# charger.net
KiCad netlist of a schematic drawn in Altium Designer
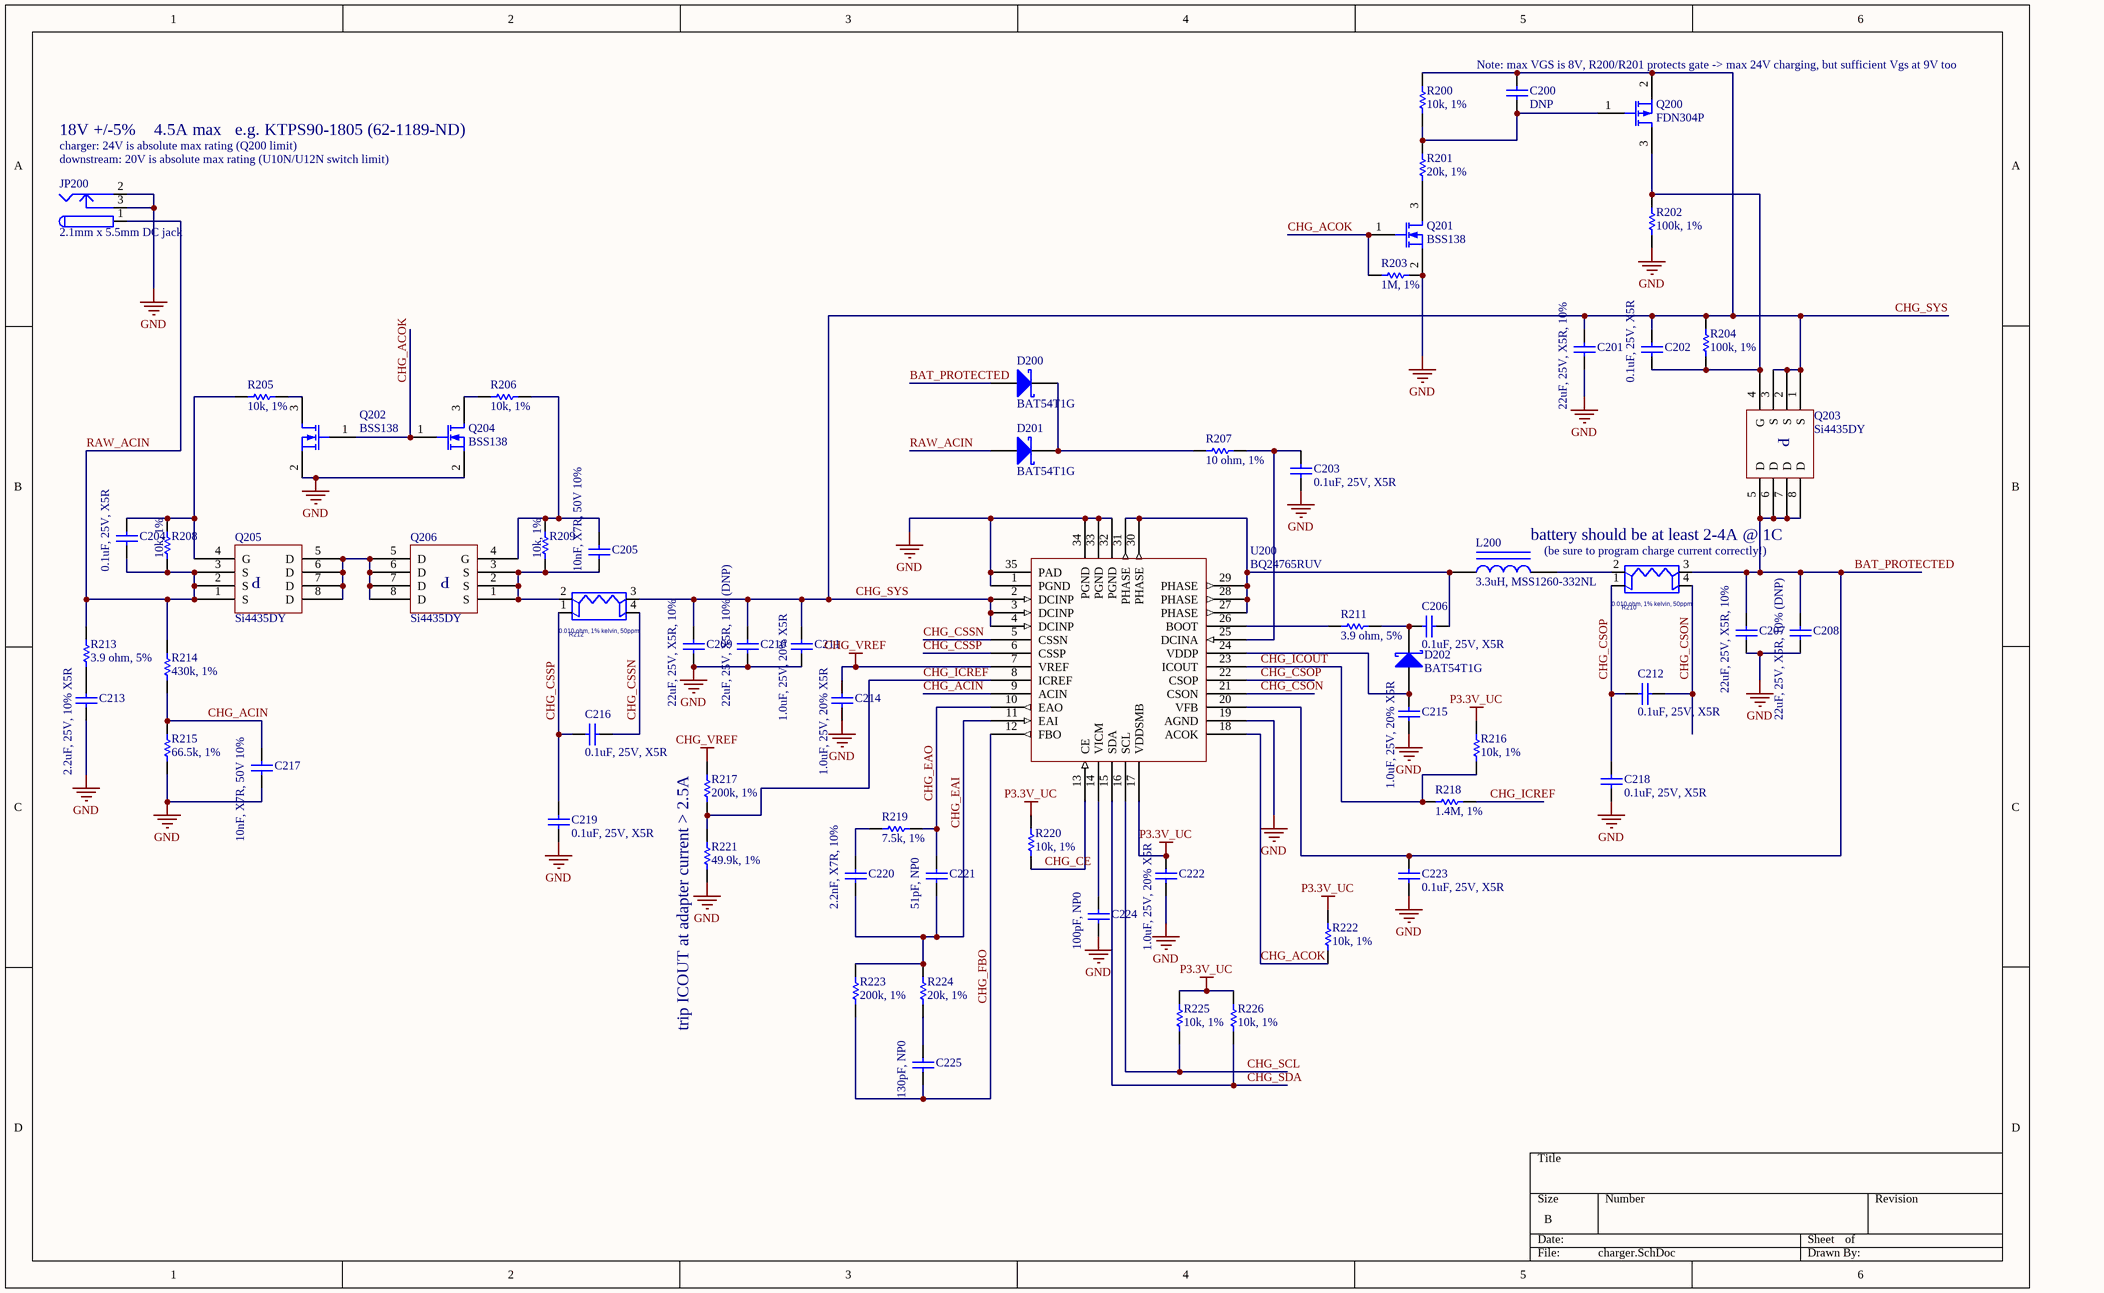
[diagram p0: charger.SchDoc]

(export (version "E")
  (design (tool "Eeschema 10.0.6"))
  (components
    (comp (ref "C200")
      (value "DNP")
      (footprint "CAPC1005N")
      (description "Capacitor (Semiconductor SIM Model)")
      (fields (field (name "PUBLISHER") "Altium Limited"))
      (libsource (lib "Miscellaneous Devices") (part "Cap Semi"))
    )
    (comp (ref "C201")
      (value "22uF, 25V, X5R, 10%")
      (footprint "CAPC3225N")
      (description "Capacitor (Semiconductor SIM Model)")
      (fields (field (name "PUBLISHER") "Altium Limited"))
      (libsource (lib "Miscellaneous Devices") (part "Cap Semi"))
    )
    (comp (ref "C202")
      (value "0.1uF, 25V, X5R")
      (footprint "CAPC1005N")
      (description "Capacitor (Semiconductor SIM Model)")
      (fields (field (name "PUBLISHER") "Altium Limited"))
      (libsource (lib "Miscellaneous Devices") (part "Cap Semi"))
    )
    (comp (ref "C203")
      (value "0.1uF, 25V, X5R")
      (footprint "CAPC1005N")
      (description "Capacitor (Semiconductor SIM Model)")
      (fields (field (name "PUBLISHER") "Altium Limited"))
      (libsource (lib "Miscellaneous Devices") (part "Cap Semi"))
    )
    (comp (ref "C204")
      (value "0.1uF, 25V, X5R")
      (footprint "CAPC1005N")
      (description "Capacitor (Semiconductor SIM Model)")
      (fields (field (name "PUBLISHER") "Altium Limited"))
      (libsource (lib "Miscellaneous Devices") (part "Cap Semi"))
    )
    (comp (ref "C205")
      (value "10nF, X7R, 50V 10%")
      (footprint "CAPC1005N")
      (description "Capacitor (Semiconductor SIM Model)")
      (fields (field (name "PUBLISHER") "Altium Limited"))
      (libsource (lib "Miscellaneous Devices") (part "Cap Semi"))
    )
    (comp (ref "C206")
      (value "0.1uF, 25V, X5R")
      (footprint "CAPC1005N")
      (description "Capacitor (Semiconductor SIM Model)")
      (fields (field (name "PUBLISHER") "Altium Limited"))
      (libsource (lib "Miscellaneous Devices") (part "Cap Semi"))
    )
    (comp (ref "C207")
      (value "22uF, 25V, X5R, 10%")
      (footprint "CAPC3225N")
      (description "Capacitor (Semiconductor SIM Model)")
      (fields (field (name "PUBLISHER") "Altium Limited"))
      (libsource (lib "Miscellaneous Devices") (part "Cap Semi"))
    )
    (comp (ref "C208")
      (value "22uF, 25V, X5R, 10% (DNP)")
      (footprint "CAPC3225N")
      (description "Capacitor (Semiconductor SIM Model)")
      (fields (field (name "PUBLISHER") "Altium Limited"))
      (libsource (lib "Miscellaneous Devices") (part "Cap Semi"))
    )
    (comp (ref "C209")
      (value "22uF, 25V, X5R, 10%")
      (footprint "CAPC3225N")
      (description "Capacitor (Semiconductor SIM Model)")
      (fields (field (name "PUBLISHER") "Altium Limited"))
      (libsource (lib "Miscellaneous Devices") (part "Cap Semi"))
    )
    (comp (ref "C210")
      (value "22uF, 25V, X5R, 10% (DNP)")
      (footprint "CAPC3225N")
      (description "Capacitor (Semiconductor SIM Model)")
      (fields (field (name "PUBLISHER") "Altium Limited"))
      (libsource (lib "Miscellaneous Devices") (part "Cap Semi"))
    )
    (comp (ref "C211")
      (value "1.0uF, 25V, 20% X5R")
      (footprint "CAPC1608N")
      (description "Capacitor (Semiconductor SIM Model)")
      (fields (field (name "PUBLISHER") "Altium Limited"))
      (libsource (lib "Miscellaneous Devices") (part "Cap Semi"))
    )
    (comp (ref "C212")
      (value "0.1uF, 25V, X5R")
      (footprint "CAPC1005N")
      (description "Capacitor (Semiconductor SIM Model)")
      (fields (field (name "PUBLISHER") "Altium Limited"))
      (libsource (lib "Miscellaneous Devices") (part "Cap Semi"))
    )
    (comp (ref "C213")
      (value "2.2uF, 25V, 10% X5R")
      (footprint "CAPC1608N")
      (description "Capacitor (Semiconductor SIM Model)")
      (fields (field (name "PUBLISHER") "Altium Limited"))
      (libsource (lib "Miscellaneous Devices") (part "Cap Semi"))
    )
    (comp (ref "C214")
      (value "1.0uF, 25V, 20% X5R")
      (footprint "CAPC1608N")
      (description "Capacitor (Semiconductor SIM Model)")
      (fields (field (name "PUBLISHER") "Altium Limited"))
      (libsource (lib "Miscellaneous Devices") (part "Cap Semi"))
    )
    (comp (ref "C215")
      (value "1.0uF, 25V, 20% X5R")
      (footprint "CAPC1608N")
      (description "Capacitor (Semiconductor SIM Model)")
      (fields (field (name "PUBLISHER") "Altium Limited"))
      (libsource (lib "Miscellaneous Devices") (part "Cap Semi"))
    )
    (comp (ref "C216")
      (value "0.1uF, 25V, X5R")
      (footprint "CAPC1005N")
      (description "Capacitor (Semiconductor SIM Model)")
      (fields (field (name "PUBLISHER") "Altium Limited"))
      (libsource (lib "Miscellaneous Devices") (part "Cap Semi"))
    )
    (comp (ref "C217")
      (value "10nF, X7R, 50V 10%")
      (footprint "CAPC1005N")
      (description "Capacitor (Semiconductor SIM Model)")
      (fields (field (name "PUBLISHER") "Altium Limited"))
      (libsource (lib "Miscellaneous Devices") (part "Cap Semi"))
    )
    (comp (ref "C218")
      (value "0.1uF, 25V, X5R")
      (footprint "CAPC1005N")
      (description "Capacitor (Semiconductor SIM Model)")
      (fields (field (name "PUBLISHER") "Altium Limited"))
      (libsource (lib "Miscellaneous Devices") (part "Cap Semi"))
    )
    (comp (ref "C219")
      (value "0.1uF, 25V, X5R")
      (footprint "CAPC1005N")
      (description "Capacitor (Semiconductor SIM Model)")
      (fields (field (name "PUBLISHER") "Altium Limited"))
      (libsource (lib "Miscellaneous Devices") (part "Cap Semi"))
    )
    (comp (ref "C220")
      (value "2.2nF, X7R, 10%")
      (footprint "CAPC1005N")
      (description "Capacitor (Semiconductor SIM Model)")
      (fields (field (name "PUBLISHER") "Altium Limited"))
      (libsource (lib "Miscellaneous Devices") (part "Cap Semi"))
    )
    (comp (ref "C221")
      (value "51pF, NP0")
      (footprint "CAPC1005N")
      (description "Capacitor (Semiconductor SIM Model)")
      (fields (field (name "PUBLISHER") "Altium Limited"))
      (libsource (lib "Miscellaneous Devices") (part "Cap Semi"))
    )
    (comp (ref "C222")
      (value "1.0uF, 25V, 20% X5R")
      (footprint "CAPC1608N")
      (description "Capacitor (Semiconductor SIM Model)")
      (fields (field (name "PUBLISHER") "Altium Limited"))
      (libsource (lib "Miscellaneous Devices") (part "Cap Semi"))
    )
    (comp (ref "C223")
      (value "0.1uF, 25V, X5R")
      (footprint "CAPC1005N")
      (description "Capacitor (Semiconductor SIM Model)")
      (fields (field (name "PUBLISHER") "Altium Limited"))
      (libsource (lib "Miscellaneous Devices") (part "Cap Semi"))
    )
    (comp (ref "C224")
      (value "100pF, NP0")
      (footprint "CAPC1005N")
      (description "Capacitor (Semiconductor SIM Model)")
      (fields (field (name "PUBLISHER") "Altium Limited"))
      (libsource (lib "Miscellaneous Devices") (part "Cap Semi"))
    )
    (comp (ref "C225")
      (value "130pF, NP0")
      (footprint "CAPC1005N")
      (description "Capacitor (Semiconductor SIM Model)")
      (fields (field (name "PUBLISHER") "Altium Limited"))
      (libsource (lib "Miscellaneous Devices") (part "Cap Semi"))
    )
    (comp (ref "D200")
      (value "BAT54T1G")
      (footprint "SOD123")
      (description "Schottky Diode")
      (fields (field (name "PUBLISHER") "Altium Limited"))
      (libsource (lib "Miscellaneous Devices") (part "D Schottky"))
    )
    (comp (ref "D201")
      (value "BAT54T1G")
      (footprint "SOD123")
      (description "Schottky Diode")
      (fields (field (name "PUBLISHER") "Altium Limited"))
      (libsource (lib "Miscellaneous Devices") (part "D Schottky"))
    )
    (comp (ref "D202")
      (value "BAT54T1G")
      (footprint "SOD123")
      (description "Schottky Diode")
      (fields (field (name "PUBLISHER") "Altium Limited"))
      (libsource (lib "Miscellaneous Devices") (part "D Schottky"))
    )
    (comp (ref "JP200")
      (value "2.1mm x 5.5mm DC jack")
      (footprint "CUI_PJ_002AH_SMT")
      (description "Low Voltage Power Supply Connector")
      (fields (field (name "PUBLISHER") "Altium Limited"))
      (libsource (lib "Miscellaneous Connectors") (part "PWR2.5"))
    )
    (comp (ref "L200")
      (value "3.3uH, MSS1260-332NL")
      (footprint "COILCRAFT_MSS1048")
      (description "Magnetic-Core Inductor")
      (fields (field (name "PUBLISHER") "Altium Limited"))
      (libsource (lib "Miscellaneous Devices") (part "Inductor Iron"))
    )
    (comp (ref "Q200")
      (value "FDN304P")
      (footprint "SOT23-3N")
      (description "P-Channel MOSFET")
      (fields (field (name "PUBLISHER") "Altium Limited"))
      (libsource (lib "Miscellaneous Devices") (part "MOSFET-P"))
    )
    (comp (ref "Q201")
      (value "BSS138")
      (footprint "SOT23-3N")
      (description "N-Channel MOSFET")
      (fields (field (name "PUBLISHER") "Altium Limited"))
      (libsource (lib "Miscellaneous Devices") (part "MOSFET-N"))
    )
    (comp (ref "Q202")
      (value "BSS138")
      (footprint "SOT23-3N")
      (description "N-Channel MOSFET")
      (fields (field (name "PUBLISHER") "Altium Limited"))
      (libsource (lib "Miscellaneous Devices") (part "MOSFET-N"))
    )
    (comp (ref "Q203")
      (value "Si4435DY")
      (footprint "SOIC127P600-8AN")
      (description "Singre P-channel FET, 8A, 30V")
      (libsource (lib "") (part "Si4435DY_2"))
    )
    (comp (ref "Q204")
      (value "BSS138")
      (footprint "SOT23-3N")
      (description "N-Channel MOSFET")
      (fields (field (name "PUBLISHER") "Altium Limited"))
      (libsource (lib "Miscellaneous Devices") (part "MOSFET-N"))
    )
    (comp (ref "Q205")
      (value "Si4435DY")
      (footprint "SOIC127P600-8AN")
      (description "Singre P-channel FET, 8A, 30V")
      (libsource (lib "") (part "Si4435DY_1"))
    )
    (comp (ref "Q206")
      (value "Si4435DY")
      (footprint "SOIC127P600-8AN")
      (description "Singre P-channel FET, 8A, 30V")
      (libsource (lib "commonsch") (part "Si4435DY"))
    )
    (comp (ref "R200")
      (value "10k, 1%")
      (footprint "RESC1005N")
      (description "Resistor")
      (fields (field (name "PUBLISHER") "Altium Limited"))
      (libsource (lib "Miscellaneous Devices") (part "Res1"))
    )
    (comp (ref "R201")
      (value "20k, 1%")
      (footprint "RESC1005N")
      (description "Resistor")
      (fields (field (name "PUBLISHER") "Altium Limited"))
      (libsource (lib "Miscellaneous Devices") (part "Res1"))
    )
    (comp (ref "R202")
      (value "100k, 1%")
      (footprint "RESC1005N")
      (description "Resistor")
      (fields (field (name "PUBLISHER") "Altium Limited"))
      (libsource (lib "Miscellaneous Devices") (part "Res1"))
    )
    (comp (ref "R203")
      (value "1M, 1%")
      (footprint "RESC1005N")
      (description "Resistor")
      (fields (field (name "PUBLISHER") "Altium Limited"))
      (libsource (lib "Miscellaneous Devices") (part "Res1"))
    )
    (comp (ref "R204")
      (value "100k, 1%")
      (footprint "RESC1005N")
      (description "Resistor")
      (fields (field (name "PUBLISHER") "Altium Limited"))
      (libsource (lib "Miscellaneous Devices") (part "Res1"))
    )
    (comp (ref "R205")
      (value "10k, 1%")
      (footprint "RESC1005N")
      (description "Resistor")
      (fields (field (name "PUBLISHER") "Altium Limited"))
      (libsource (lib "Miscellaneous Devices") (part "Res1"))
    )
    (comp (ref "R206")
      (value "10k, 1%")
      (footprint "RESC1005N")
      (description "Resistor")
      (fields (field (name "PUBLISHER") "Altium Limited"))
      (libsource (lib "Miscellaneous Devices") (part "Res1"))
    )
    (comp (ref "R207")
      (value "10 ohm, 1%")
      (footprint "RESC1005N")
      (description "Resistor")
      (fields (field (name "PUBLISHER") "Altium Limited"))
      (libsource (lib "Miscellaneous Devices") (part "Res1"))
    )
    (comp (ref "R208")
      (value "10k, 1%")
      (footprint "RESC1005N")
      (description "Resistor")
      (fields (field (name "PUBLISHER") "Altium Limited"))
      (libsource (lib "Miscellaneous Devices") (part "Res1"))
    )
    (comp (ref "R209")
      (value "10k, 1%")
      (footprint "RESC1005N")
      (description "Resistor")
      (fields (field (name "PUBLISHER") "Altium Limited"))
      (libsource (lib "Miscellaneous Devices") (part "Res1"))
    )
    (comp (ref "R210")
      (value "0.010 ohm, 1% kelvin, 50ppm")
      (fields
        (field (name "PART_NUMBER") "R00034-001")
        (field (name "TOLERANCE") "?")
        (field (name "MFG") "OHMITE")
      )
      (libsource (lib "*") (part "RES_4TERM"))
    )
    (comp (ref "R211")
      (value "3.9 ohm, 5%")
      (footprint "RESC1005N")
      (description "Resistor")
      (fields (field (name "PUBLISHER") "Altium Limited"))
      (libsource (lib "Miscellaneous Devices") (part "Res1"))
    )
    (comp (ref "R212")
      (value "0.010 ohm, 1% kelvin, 50ppm")
      (fields
        (field (name "PART_NUMBER") "R00034-001")
        (field (name "TOLERANCE") "?")
        (field (name "MFG") "OHMITE")
      )
      (libsource (lib "*") (part "RES_4TERM"))
    )
    (comp (ref "R213")
      (value "3.9 ohm, 5%")
      (footprint "RESC1005N")
      (description "Resistor")
      (fields (field (name "PUBLISHER") "Altium Limited"))
      (libsource (lib "Miscellaneous Devices") (part "Res1"))
    )
    (comp (ref "R214")
      (value "430k, 1%")
      (footprint "RESC1005N")
      (description "Resistor")
      (fields (field (name "PUBLISHER") "Altium Limited"))
      (libsource (lib "Miscellaneous Devices") (part "Res1"))
    )
    (comp (ref "R215")
      (value "66.5k, 1%")
      (footprint "RESC1005N")
      (description "Resistor")
      (fields (field (name "PUBLISHER") "Altium Limited"))
      (libsource (lib "Miscellaneous Devices") (part "Res1"))
    )
    (comp (ref "R216")
      (value "10k, 1%")
      (footprint "RESC1005N")
      (description "Resistor")
      (fields (field (name "PUBLISHER") "Altium Limited"))
      (libsource (lib "Miscellaneous Devices") (part "Res1"))
    )
    (comp (ref "R217")
      (value "200k, 1%")
      (footprint "RESC1005N")
      (description "Resistor")
      (fields (field (name "PUBLISHER") "Altium Limited"))
      (libsource (lib "Miscellaneous Devices") (part "Res1"))
    )
    (comp (ref "R218")
      (value "1.4M, 1%")
      (footprint "RESC1005N")
      (description "Resistor")
      (fields (field (name "PUBLISHER") "Altium Limited"))
      (libsource (lib "Miscellaneous Devices") (part "Res1"))
    )
    (comp (ref "R219")
      (value "7.5k, 1%")
      (footprint "RESC1005N")
      (description "Resistor")
      (fields (field (name "PUBLISHER") "Altium Limited"))
      (libsource (lib "Miscellaneous Devices") (part "Res1"))
    )
    (comp (ref "R220")
      (value "10k, 1%")
      (footprint "RESC1005N")
      (description "Resistor")
      (fields (field (name "PUBLISHER") "Altium Limited"))
      (libsource (lib "Miscellaneous Devices") (part "Res1"))
    )
    (comp (ref "R221")
      (value "49.9k, 1%")
      (footprint "RESC1005N")
      (description "Resistor")
      (fields (field (name "PUBLISHER") "Altium Limited"))
      (libsource (lib "Miscellaneous Devices") (part "Res1"))
    )
    (comp (ref "R222")
      (value "10k, 1%")
      (footprint "RESC1005N")
      (description "Resistor")
      (fields (field (name "PUBLISHER") "Altium Limited"))
      (libsource (lib "Miscellaneous Devices") (part "Res1"))
    )
    (comp (ref "R223")
      (value "200k, 1%")
      (footprint "RESC1005N")
      (description "Resistor")
      (fields (field (name "PUBLISHER") "Altium Limited"))
      (libsource (lib "Miscellaneous Devices") (part "Res1"))
    )
    (comp (ref "R224")
      (value "20k, 1%")
      (footprint "RESC1005N")
      (description "Resistor")
      (fields (field (name "PUBLISHER") "Altium Limited"))
      (libsource (lib "Miscellaneous Devices") (part "Res1"))
    )
    (comp (ref "R225")
      (value "10k, 1%")
      (footprint "RESC1005N")
      (description "Resistor")
      (fields (field (name "PUBLISHER") "Altium Limited"))
      (libsource (lib "Miscellaneous Devices") (part "Res1"))
    )
    (comp (ref "R226")
      (value "10k, 1%")
      (footprint "RESC1005N")
      (description "Resistor")
      (fields (field (name "PUBLISHER") "Altium Limited"))
      (libsource (lib "Miscellaneous Devices") (part "Res1"))
    )
    (comp (ref "U200")
      (value "BQ24765RUV")
      (footprint "TI_R-PVQFN-N34")
      (description "SMBus-controlled battery charger with integrated FETs")
      (libsource (lib "commonsch") (part "BQ24765RUV"))
    )
  )
  (nets
    (net (code "1") (name "/BAT_PROTECTED") (class "Default")
      (node (ref "C207") (pin "1") (pinfunction "1_1") (pintype "passive"))
      (node (ref "C208") (pin "1") (pinfunction "1_1") (pintype "passive"))
      (node (ref "C223") (pin "2") (pinfunction "2_2") (pintype "passive"))
      (node (ref "D200") (pin "1") (pinfunction "A_1") (pintype "passive"))
      (node (ref "Q203") (pin "5") (pinfunction "D_5") (pintype "passive"))
      (node (ref "Q203") (pin "6") (pinfunction "D_6") (pintype "passive"))
      (node (ref "Q203") (pin "7") (pinfunction "D_7") (pintype "passive"))
      (node (ref "Q203") (pin "8") (pinfunction "D_8") (pintype "passive"))
      (node (ref "R210") (pin "3") (pinfunction "3_3") (pintype "bidirectional"))
      (node (ref "U200") (pin "20") (pinfunction "VFB_20") (pintype "passive"))
    )
    (net (code "2") (name "/CHG_ACIN") (class "Default")
      (node (ref "C217") (pin "1") (pinfunction "1_1") (pintype "passive"))
      (node (ref "R214") (pin "2") (pinfunction "2_2") (pintype "passive"))
      (node (ref "R215") (pin "1") (pinfunction "1_1") (pintype "passive"))
      (node (ref "U200") (pin "9") (pinfunction "ACIN_9") (pintype "passive"))
    )
    (net (code "3") (name "/CHG_ACOK") (class "Default")
      (node (ref "Q201") (pin "1") (pinfunction "G_1") (pintype "passive"))
      (node (ref "Q202") (pin "1") (pinfunction "G_1") (pintype "passive"))
      (node (ref "Q204") (pin "1") (pinfunction "G_1") (pintype "passive"))
      (node (ref "R203") (pin "2") (pinfunction "2_2") (pintype "passive"))
      (node (ref "R222") (pin "2") (pinfunction "2_2") (pintype "passive"))
      (node (ref "U200") (pin "18") (pinfunction "ACOK_18") (pintype "open_collector"))
    )
    (net (code "4") (name "/CHG_CE") (class "Default")
      (node (ref "R220") (pin "2") (pinfunction "2_2") (pintype "passive"))
      (node (ref "U200") (pin "13") (pinfunction "CE_13") (pintype "input"))
    )
    (net (code "5") (name "/CHG_CSON") (class "Default")
      (node (ref "C212") (pin "1") (pinfunction "1_1") (pintype "passive"))
      (node (ref "R210") (pin "4") (pinfunction "4_4") (pintype "bidirectional"))
      (node (ref "U200") (pin "21") (pinfunction "CSON_21") (pintype "passive"))
    )
    (net (code "6") (name "/CHG_CSOP") (class "Default")
      (node (ref "C212") (pin "2") (pinfunction "2_2") (pintype "passive"))
      (node (ref "C218") (pin "2") (pinfunction "2_2") (pintype "passive"))
      (node (ref "R210") (pin "1") (pinfunction "1_1") (pintype "bidirectional"))
      (node (ref "U200") (pin "22") (pinfunction "CSOP_22") (pintype "passive"))
    )
    (net (code "7") (name "/CHG_CSSN") (class "Default")
      (node (ref "C216") (pin "2") (pinfunction "2_2") (pintype "passive"))
      (node (ref "R212") (pin "4") (pinfunction "4_4") (pintype "bidirectional"))
      (node (ref "U200") (pin "5") (pinfunction "CSSN_5") (pintype "passive"))
    )
    (net (code "8") (name "/CHG_CSSP") (class "Default")
      (node (ref "C216") (pin "1") (pinfunction "1_1") (pintype "passive"))
      (node (ref "C219") (pin "1") (pinfunction "1_1") (pintype "passive"))
      (node (ref "R212") (pin "1") (pinfunction "1_1") (pintype "bidirectional"))
      (node (ref "U200") (pin "6") (pinfunction "CSSP_6") (pintype "passive"))
    )
    (net (code "9") (name "/CHG_EAI") (class "Default")
      (node (ref "C220") (pin "2") (pinfunction "2_2") (pintype "passive"))
      (node (ref "C221") (pin "2") (pinfunction "2_2") (pintype "passive"))
      (node (ref "R223") (pin "1") (pinfunction "1_1") (pintype "passive"))
      (node (ref "R224") (pin "1") (pinfunction "1_1") (pintype "passive"))
      (node (ref "U200") (pin "11") (pinfunction "EAI_11") (pintype "input"))
    )
    (net (code "10") (name "/CHG_EAO") (class "Default")
      (node (ref "C221") (pin "1") (pinfunction "1_1") (pintype "passive"))
      (node (ref "R219") (pin "2") (pinfunction "2_2") (pintype "passive"))
      (node (ref "U200") (pin "10") (pinfunction "EAO_10") (pintype "output"))
    )
    (net (code "11") (name "/CHG_FBO") (class "Default")
      (node (ref "C225") (pin "2") (pinfunction "2_2") (pintype "passive"))
      (node (ref "R223") (pin "2") (pinfunction "2_2") (pintype "passive"))
      (node (ref "U200") (pin "12") (pinfunction "FBO_12") (pintype "output"))
    )
    (net (code "12") (name "/CHG_ICOUT") (class "Default")
      (node (ref "R216") (pin "2") (pinfunction "2_2") (pintype "passive"))
      (node (ref "R218") (pin "2") (pinfunction "2_2") (pintype "passive"))
      (node (ref "U200") (pin "23") (pinfunction "ICOUT_23") (pintype "open_collector"))
    )
    (net (code "13") (name "/CHG_ICREF") (class "Default")
      (node (ref "R217") (pin "2") (pinfunction "2_2") (pintype "passive"))
      (node (ref "R218") (pin "1") (pinfunction "1_1") (pintype "passive"))
      (node (ref "R221") (pin "1") (pinfunction "1_1") (pintype "passive"))
      (node (ref "U200") (pin "8") (pinfunction "ICREF_8") (pintype "passive"))
    )
    (net (code "14") (name "/CHG_SCL") (class "Default")
      (node (ref "R225") (pin "2") (pinfunction "2_2") (pintype "passive"))
      (node (ref "U200") (pin "16") (pinfunction "SCL_16") (pintype "open_emitter"))
    )
    (net (code "15") (name "/CHG_SDA") (class "Default")
      (node (ref "R226") (pin "2") (pinfunction "2_2") (pintype "passive"))
      (node (ref "U200") (pin "15") (pinfunction "SDA_15") (pintype "open_emitter"))
    )
    (net (code "16") (name "/CHG_SYS") (class "Default")
      (node (ref "C200") (pin "2") (pinfunction "2_2") (pintype "passive"))
      (node (ref "C201") (pin "1") (pinfunction "1_1") (pintype "passive"))
      (node (ref "C202") (pin "1") (pinfunction "1_1") (pintype "passive"))
      (node (ref "C209") (pin "1") (pinfunction "1_1") (pintype "passive"))
      (node (ref "C210") (pin "1") (pinfunction "1_1") (pintype "passive"))
      (node (ref "C211") (pin "1") (pinfunction "1_1") (pintype "passive"))
      (node (ref "Q200") (pin "2") (pinfunction "S_2") (pintype "passive"))
      (node (ref "Q203") (pin "1") (pinfunction "S_1") (pintype "passive"))
      (node (ref "Q203") (pin "2") (pinfunction "S_2") (pintype "passive"))
      (node (ref "Q203") (pin "3") (pinfunction "S_3") (pintype "passive"))
      (node (ref "R200") (pin "1") (pinfunction "1_1") (pintype "passive"))
      (node (ref "R204") (pin "1") (pinfunction "1_1") (pintype "passive"))
      (node (ref "R212") (pin "3") (pinfunction "3_3") (pintype "bidirectional"))
      (node (ref "U200") (pin "2") (pinfunction "DCINP_2") (pintype "input"))
      (node (ref "U200") (pin "3") (pinfunction "DCINP_3") (pintype "input"))
      (node (ref "U200") (pin "4") (pinfunction "DCINP_4") (pintype "input"))
    )
    (net (code "17") (name "/RAW_ACIN") (class "Default")
      (node (ref "C204") (pin "2") (pinfunction "2_2") (pintype "passive"))
      (node (ref "D201") (pin "1") (pinfunction "A_1") (pintype "passive"))
      (node (ref "JP200") (pin "1") (pintype "power_in"))
      (node (ref "Q205") (pin "1") (pinfunction "S_1") (pintype "passive"))
      (node (ref "Q205") (pin "2") (pinfunction "S_2") (pintype "passive"))
      (node (ref "Q205") (pin "3") (pinfunction "S_3") (pintype "passive"))
      (node (ref "R208") (pin "1") (pinfunction "1_1") (pintype "passive"))
      (node (ref "R213") (pin "1") (pinfunction "1_1") (pintype "passive"))
      (node (ref "R214") (pin "1") (pinfunction "1_1") (pintype "passive"))
    )
    (net (code "18") (name "CHG_VREF") (class "Default")
      (node (ref "C214") (pin "1") (pinfunction "1_1") (pintype "passive"))
      (node (ref "R217") (pin "1") (pinfunction "1_1") (pintype "passive"))
      (node (ref "U200") (pin "7") (pinfunction "VREF_7") (pintype "power_in"))
    )
    (net (code "19") (name "GND") (class "Default")
      (node (ref "C201") (pin "2") (pinfunction "2_2") (pintype "passive"))
      (node (ref "C203") (pin "2") (pinfunction "2_2") (pintype "passive"))
      (node (ref "C207") (pin "2") (pinfunction "2_2") (pintype "passive"))
      (node (ref "C208") (pin "2") (pinfunction "2_2") (pintype "passive"))
      (node (ref "C209") (pin "2") (pinfunction "2_2") (pintype "passive"))
      (node (ref "C210") (pin "2") (pinfunction "2_2") (pintype "passive"))
      (node (ref "C211") (pin "2") (pinfunction "2_2") (pintype "passive"))
      (node (ref "C213") (pin "2") (pinfunction "2_2") (pintype "passive"))
      (node (ref "C214") (pin "2") (pinfunction "2_2") (pintype "passive"))
      (node (ref "C215") (pin "2") (pinfunction "2_2") (pintype "passive"))
      (node (ref "C217") (pin "2") (pinfunction "2_2") (pintype "passive"))
      (node (ref "C218") (pin "1") (pinfunction "1_1") (pintype "passive"))
      (node (ref "C219") (pin "2") (pinfunction "2_2") (pintype "passive"))
      (node (ref "C222") (pin "2") (pinfunction "2_2") (pintype "passive"))
      (node (ref "C223") (pin "1") (pinfunction "1_1") (pintype "passive"))
      (node (ref "C224") (pin "2") (pinfunction "2_2") (pintype "passive"))
      (node (ref "JP200") (pin "2") (pintype "power_in"))
      (node (ref "JP200") (pin "3") (pintype "power_in"))
      (node (ref "Q201") (pin "2") (pinfunction "S_2") (pintype "passive"))
      (node (ref "Q202") (pin "2") (pinfunction "S_2") (pintype "passive"))
      (node (ref "Q204") (pin "2") (pinfunction "S_2") (pintype "passive"))
      (node (ref "R202") (pin "2") (pinfunction "2_2") (pintype "passive"))
      (node (ref "R203") (pin "1") (pinfunction "1_1") (pintype "passive"))
      (node (ref "R215") (pin "2") (pinfunction "2_2") (pintype "passive"))
      (node (ref "R221") (pin "2") (pinfunction "2_2") (pintype "passive"))
      (node (ref "U200") (pin "1") (pinfunction "PGND_1") (pintype "power_in"))
      (node (ref "U200") (pin "19") (pinfunction "AGND_19") (pintype "power_in"))
      (node (ref "U200") (pin "32") (pinfunction "PGND_32") (pintype "power_in"))
      (node (ref "U200") (pin "33") (pinfunction "PGND_33") (pintype "power_in"))
      (node (ref "U200") (pin "34") (pinfunction "PGND_34") (pintype "power_in"))
      (node (ref "U200") (pin "35") (pinfunction "PAD_35") (pintype "power_in"))
    )
    (net (code "20") (name "Net-(C205-Pad2)") (class "Default")
      (node (ref "C205") (pin "2") (pinfunction "2_2") (pintype "passive"))
      (node (ref "Q206") (pin "1") (pinfunction "S_1") (pintype "passive"))
      (node (ref "Q206") (pin "2") (pinfunction "S_2") (pintype "passive"))
      (node (ref "Q206") (pin "3") (pinfunction "S_3") (pintype "passive"))
      (node (ref "R209") (pin "1") (pinfunction "1_1") (pintype "passive"))
      (node (ref "R212") (pin "2") (pinfunction "2_2") (pintype "bidirectional"))
    )
    (net (code "21") (name "Net-(C206-Pad2)") (class "Default")
      (node (ref "C206") (pin "2") (pinfunction "2_2") (pintype "passive"))
      (node (ref "L200") (pin "1") (pinfunction "1_1") (pintype "passive"))
      (node (ref "U200") (pin "27") (pinfunction "PHASE_27") (pintype "output"))
      (node (ref "U200") (pin "28") (pinfunction "PHASE_28") (pintype "output"))
      (node (ref "U200") (pin "29") (pinfunction "PHASE_29") (pintype "output"))
      (node (ref "U200") (pin "30") (pinfunction "PHASE_30") (pintype "output"))
      (node (ref "U200") (pin "31") (pinfunction "PHASE_31") (pintype "output"))
    )
    (net (code "22") (name "Net-(C213-Pad1)") (class "Default")
      (node (ref "C213") (pin "1") (pinfunction "1_1") (pintype "passive"))
      (node (ref "R213") (pin "2") (pinfunction "2_2") (pintype "passive"))
    )
    (net (code "23") (name "Net-(C220-Pad1)") (class "Default")
      (node (ref "C220") (pin "1") (pinfunction "1_1") (pintype "passive"))
      (node (ref "R219") (pin "1") (pinfunction "1_1") (pintype "passive"))
    )
    (net (code "24") (name "Net-(C225-Pad1)") (class "Default")
      (node (ref "C225") (pin "1") (pinfunction "1_1") (pintype "passive"))
      (node (ref "R224") (pin "2") (pinfunction "2_2") (pintype "passive"))
    )
    (net (code "25") (name "Net-(D200-K)") (class "Default")
      (node (ref "D200") (pin "2") (pinfunction "K_2") (pintype "passive"))
      (node (ref "D201") (pin "2") (pinfunction "K_2") (pintype "passive"))
      (node (ref "R207") (pin "1") (pinfunction "1_1") (pintype "passive"))
    )
    (net (code "26") (name "Net-(D202-A)") (class "Default")
      (node (ref "C215") (pin "1") (pinfunction "1_1") (pintype "passive"))
      (node (ref "D202") (pin "1") (pinfunction "A_1") (pintype "passive"))
      (node (ref "U200") (pin "24") (pinfunction "VDDP_24") (pintype "power_in"))
    )
    (net (code "27") (name "Net-(D202-K)") (class "Default")
      (node (ref "C206") (pin "1") (pinfunction "1_1") (pintype "passive"))
      (node (ref "D202") (pin "2") (pinfunction "K_2") (pintype "passive"))
      (node (ref "R211") (pin "2") (pinfunction "2_2") (pintype "passive"))
    )
    (net (code "28") (name "Net-(L200-Pad2)") (class "Default")
      (node (ref "L200") (pin "2") (pinfunction "2_2") (pintype "passive"))
      (node (ref "R210") (pin "2") (pinfunction "2_2") (pintype "bidirectional"))
    )
    (net (code "29") (name "Net-(Q200-D)") (class "Default")
      (node (ref "C202") (pin "2") (pinfunction "2_2") (pintype "passive"))
      (node (ref "Q200") (pin "3") (pinfunction "D_3") (pintype "passive"))
      (node (ref "Q203") (pin "4") (pinfunction "G_4") (pintype "passive"))
      (node (ref "R202") (pin "1") (pinfunction "1_1") (pintype "passive"))
      (node (ref "R204") (pin "2") (pinfunction "2_2") (pintype "passive"))
    )
    (net (code "30") (name "Net-(Q200-G)") (class "Default")
      (node (ref "C200") (pin "1") (pinfunction "1_1") (pintype "passive"))
      (node (ref "Q200") (pin "1") (pinfunction "G_1") (pintype "passive"))
      (node (ref "R200") (pin "2") (pinfunction "2_2") (pintype "passive"))
      (node (ref "R201") (pin "1") (pinfunction "1_1") (pintype "passive"))
    )
    (net (code "31") (name "Net-(Q201-D)") (class "Default")
      (node (ref "Q201") (pin "3") (pinfunction "D_3") (pintype "passive"))
      (node (ref "R201") (pin "2") (pinfunction "2_2") (pintype "passive"))
    )
    (net (code "32") (name "Net-(Q202-D)") (class "Default")
      (node (ref "Q202") (pin "3") (pinfunction "D_3") (pintype "passive"))
      (node (ref "R205") (pin "2") (pinfunction "2_2") (pintype "passive"))
    )
    (net (code "33") (name "Net-(Q204-D)") (class "Default")
      (node (ref "Q204") (pin "3") (pinfunction "D_3") (pintype "passive"))
      (node (ref "R206") (pin "1") (pinfunction "1_1") (pintype "passive"))
    )
    (net (code "34") (name "Net-(Q205-D-Pad5)") (class "Default")
      (node (ref "Q205") (pin "5") (pinfunction "D_5") (pintype "passive"))
      (node (ref "Q205") (pin "6") (pinfunction "D_6") (pintype "passive"))
      (node (ref "Q205") (pin "7") (pinfunction "D_7") (pintype "passive"))
      (node (ref "Q205") (pin "8") (pinfunction "D_8") (pintype "passive"))
      (node (ref "Q206") (pin "5") (pinfunction "D_5") (pintype "passive"))
      (node (ref "Q206") (pin "6") (pinfunction "D_6") (pintype "passive"))
      (node (ref "Q206") (pin "7") (pinfunction "D_7") (pintype "passive"))
      (node (ref "Q206") (pin "8") (pinfunction "D_8") (pintype "passive"))
    )
    (net (code "35") (name "Net-(Q205-G)") (class "Default")
      (node (ref "C204") (pin "1") (pinfunction "1_1") (pintype "passive"))
      (node (ref "Q205") (pin "4") (pinfunction "G_4") (pintype "passive"))
      (node (ref "R205") (pin "1") (pinfunction "1_1") (pintype "passive"))
      (node (ref "R208") (pin "2") (pinfunction "2_2") (pintype "passive"))
    )
    (net (code "36") (name "Net-(Q206-G)") (class "Default")
      (node (ref "C205") (pin "1") (pinfunction "1_1") (pintype "passive"))
      (node (ref "Q206") (pin "4") (pinfunction "G_4") (pintype "passive"))
      (node (ref "R206") (pin "2") (pinfunction "2_2") (pintype "passive"))
      (node (ref "R209") (pin "2") (pinfunction "2_2") (pintype "passive"))
    )
    (net (code "37") (name "Net-(U200-BOOT)") (class "Default")
      (node (ref "R211") (pin "1") (pinfunction "1_1") (pintype "passive"))
      (node (ref "U200") (pin "26") (pinfunction "BOOT_26") (pintype "passive"))
    )
    (net (code "38") (name "Net-(U200-DCINA)") (class "Default")
      (node (ref "C203") (pin "1") (pinfunction "1_1") (pintype "passive"))
      (node (ref "R207") (pin "2") (pinfunction "2_2") (pintype "passive"))
      (node (ref "U200") (pin "25") (pinfunction "DCINA_25") (pintype "input"))
    )
    (net (code "39") (name "Net-(U200-VICM)") (class "Default")
      (node (ref "C224") (pin "1") (pinfunction "1_1") (pintype "passive"))
      (node (ref "U200") (pin "14") (pinfunction "VICM_14") (pintype "passive"))
    )
    (net (code "40") (name "P3.3V_UC") (class "Default")
      (node (ref "C222") (pin "1") (pinfunction "1_1") (pintype "passive"))
      (node (ref "R216") (pin "1") (pinfunction "1_1") (pintype "passive"))
      (node (ref "R220") (pin "1") (pinfunction "1_1") (pintype "passive"))
      (node (ref "R222") (pin "1") (pinfunction "1_1") (pintype "passive"))
      (node (ref "R225") (pin "1") (pinfunction "1_1") (pintype "passive"))
      (node (ref "R226") (pin "1") (pinfunction "1_1") (pintype "passive"))
      (node (ref "U200") (pin "17") (pinfunction "VDDSMB_17") (pintype "power_in"))
    )
  )
)
